# EVK-IRIS-W1-DEBUG_INTERFACE.net
KiCad netlist of a schematic drawn in Altium Designer
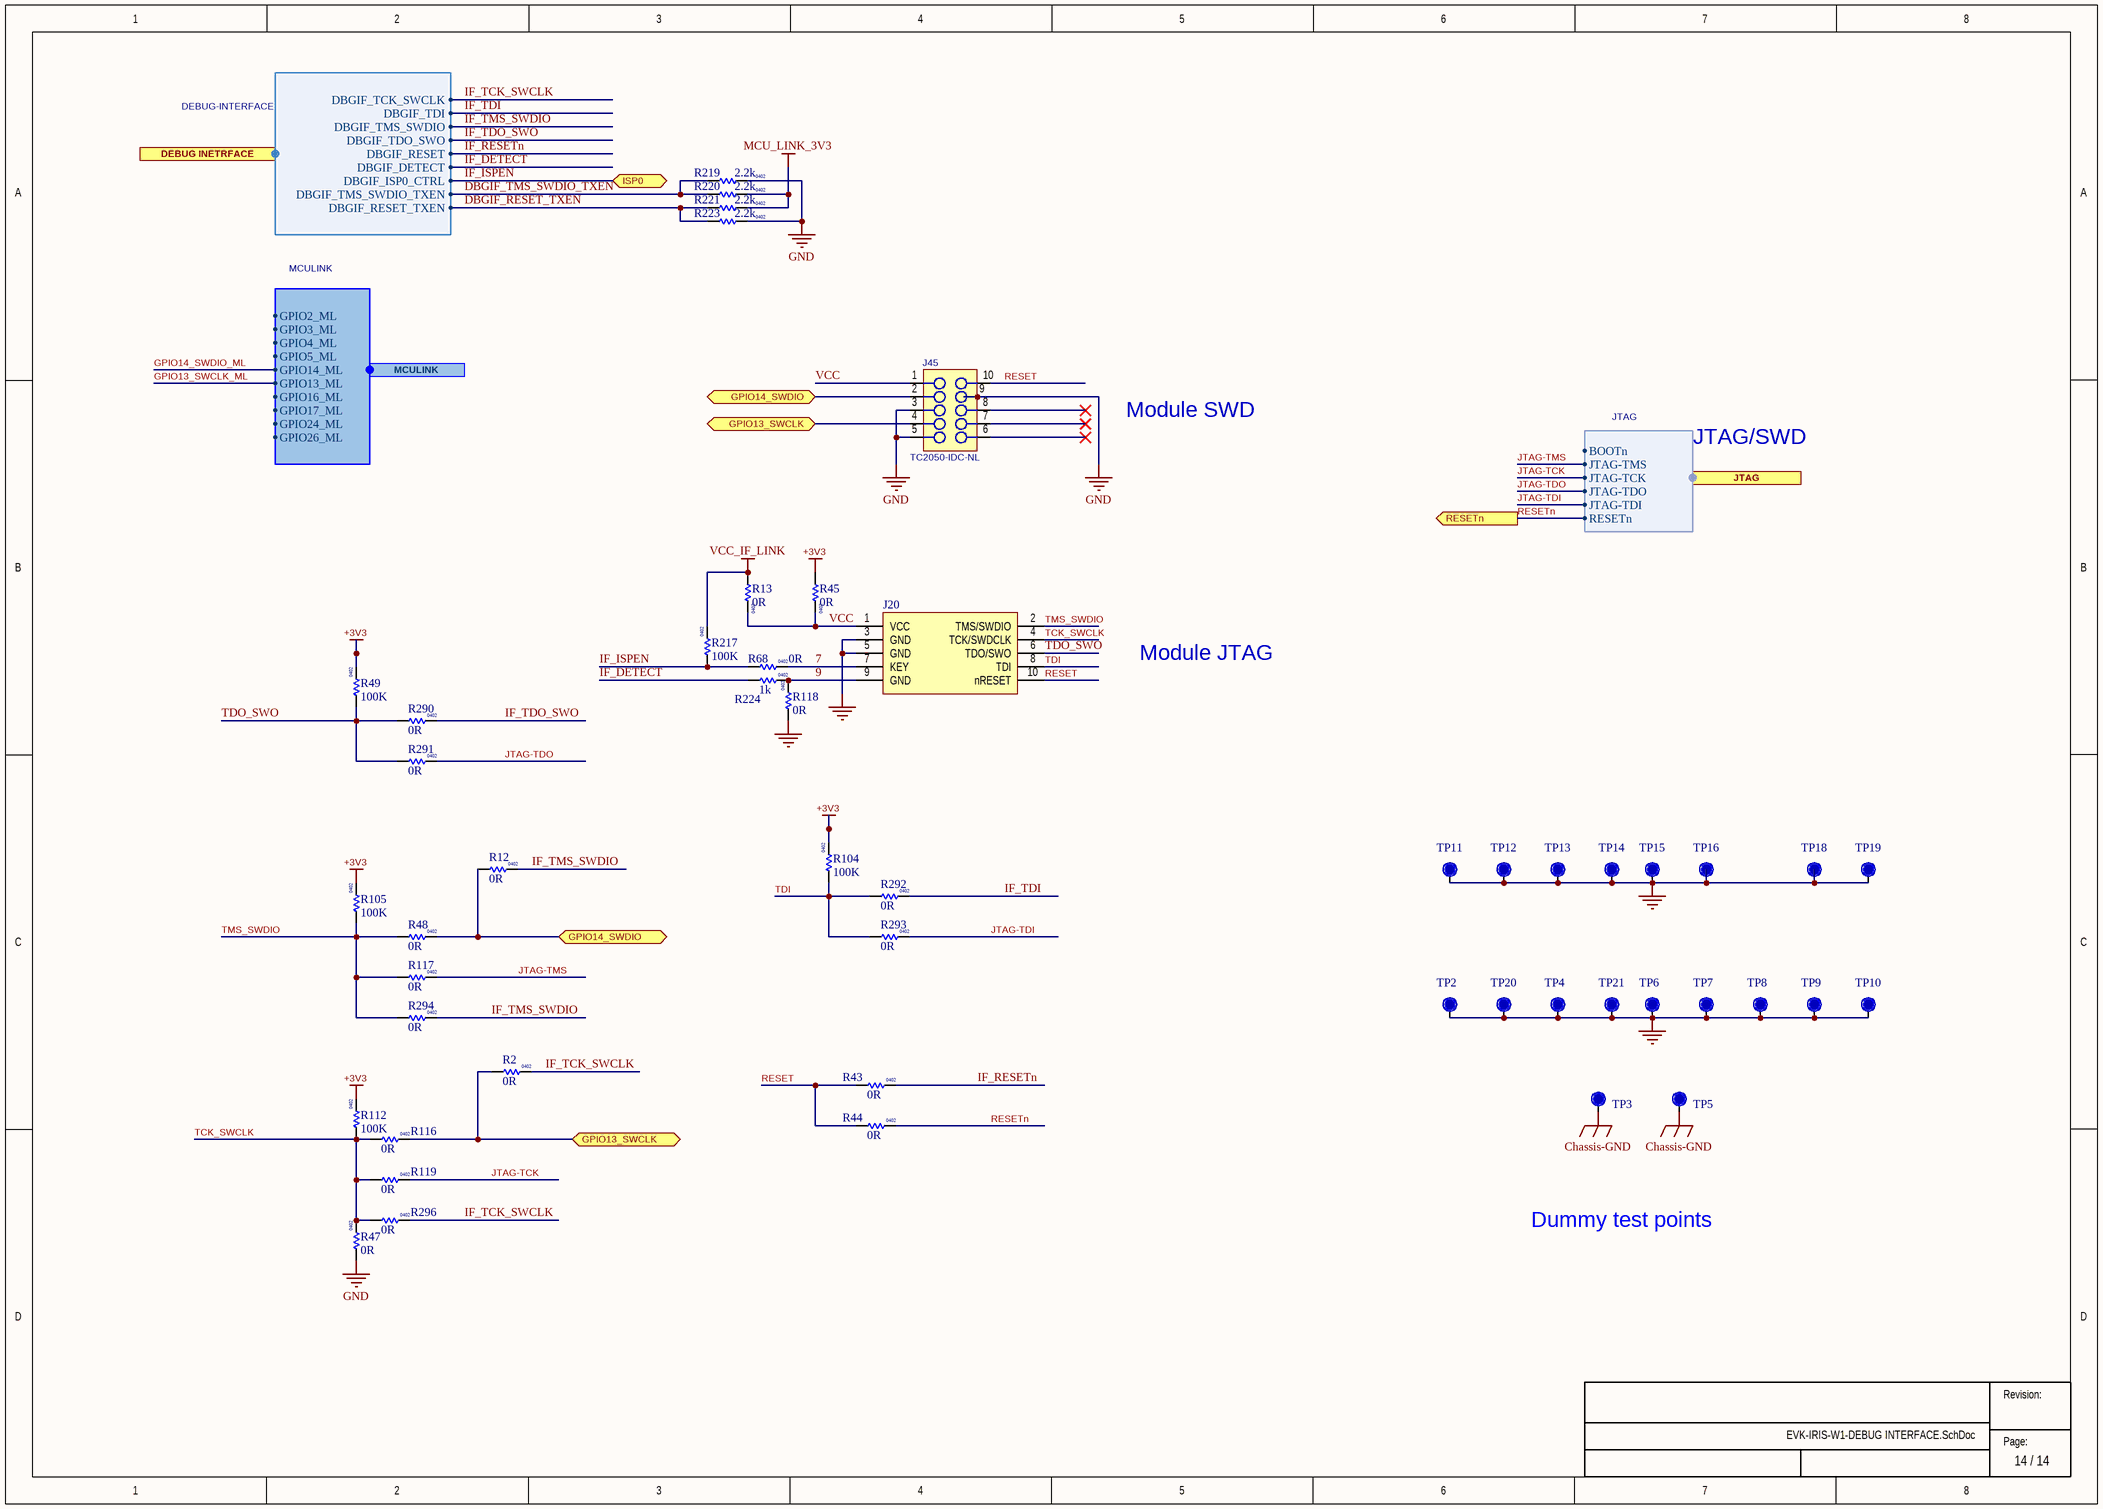
[diagram p0: EVK-IRIS-W1-DEBUG INTERFACE.SchDoc]

(export (version "E")
  (design (tool "Eeschema 10.0.6"))
  (components
    (comp (ref "J20")
      (value "130-00099")
      (footprint "HDR.050P-10Pin-2x5-SMT_Key")
      (description "Header 0.05\" 10Pin 2Row SMD Black")
      (fields (field (name "VOLTAGE") "None"))
      (libsource (lib "Arena_Parts_DB_Lib") (part "JTAG-10Pin"))
    )
    (comp (ref "J45")
      (value "TC2050-IDC-NLDNP")
      (footprint "TC2050-IDC-NL")
      (description "CON PADS FOR CBL PLUG-OF-NAILS 10-PIN NO LEGS")
      (fields
        (field (name "MANUFACTURER P/N") "TC2050-IDC-NL")
        (field (name "PART NUMBER") "TC2050-IDC-NL")
        (field (name "MANUFACTURER") "TAG Connect")
        (field (name "ADDED BY") "Paul B")
      )
      (libsource (lib "LEGACY_Rigado_AltiumLib") (part "CON-10Pin_2Row_ALT"))
    )
    (comp (ref "R2")
      (value "0R")
      (footprint "RES 0402 HD")
      (description "RES THICK FILM CHIP 0402 0R 0 100mW")
      (fields
        (field (name "SIZE") "0402")
        (field (name "PART NUMBER") "UBXH18-0003002")
        (field (name "TOLERANCE") "0")
        (field (name "EDITOR") "charlotte.biber")
        (field (name "RELEASED BY") "peter.mueller")
      )
      (libsource (lib "UBX_Parts_DB_Lib") (part "Res sm"))
    )
    (comp (ref "R12")
      (value "0R")
      (footprint "RES 0402 HD")
      (description "RES THICK FILM CHIP 0402 0R 0 100mW")
      (fields
        (field (name "SIZE") "0402")
        (field (name "PART NUMBER") "UBXH18-0003002")
        (field (name "TOLERANCE") "0")
        (field (name "EDITOR") "charlotte.biber")
        (field (name "RELEASED BY") "peter.mueller")
      )
      (libsource (lib "UBX_Parts_DB_Lib") (part "Res sm"))
    )
    (comp (ref "R13")
      (value "0R")
      (footprint "RES 0402 HD")
      (description "RES THICK FILM CHIP 0402 0R 0 100mW")
      (fields
        (field (name "SIZE") "0402")
        (field (name "PART NUMBER") "UBXH18-0003002")
        (field (name "TOLERANCE") "0")
        (field (name "EDITOR") "charlotte.biber")
        (field (name "RELEASED BY") "peter.mueller")
      )
      (libsource (lib "UBX_Parts_DB_Lib") (part "Res sm"))
    )
    (comp (ref "R43")
      (value "0R")
      (footprint "RES 0402 HD")
      (description "RES THICK FILM CHIP 0402 0R 0 100mW")
      (fields
        (field (name "SIZE") "0402")
        (field (name "PART NUMBER") "UBXH18-0003002")
        (field (name "TOLERANCE") "0")
        (field (name "EDITOR") "charlotte.biber")
        (field (name "RELEASED BY") "peter.mueller")
      )
      (libsource (lib "UBX_Parts_DB_Lib") (part "Res sm"))
    )
    (comp (ref "R44")
      (value "0R")
      (footprint "RES 0402 HD")
      (description "RES THICK FILM CHIP 0402 0R 0 100mW")
      (fields
        (field (name "SIZE") "0402")
        (field (name "PART NUMBER") "UBXH18-0003002")
        (field (name "TOLERANCE") "0")
        (field (name "EDITOR") "charlotte.biber")
        (field (name "RELEASED BY") "peter.mueller")
      )
      (libsource (lib "UBX_Parts_DB_Lib") (part "Res sm"))
    )
    (comp (ref "R45")
      (value "0R")
      (footprint "RES 0402 HD")
      (description "RES THICK FILM CHIP 0402 0R 0 100mW")
      (fields
        (field (name "SIZE") "0402")
        (field (name "PART NUMBER") "UBXH18-0003002")
        (field (name "TOLERANCE") "0")
        (field (name "EDITOR") "charlotte.biber")
        (field (name "RELEASED BY") "peter.mueller")
      )
      (libsource (lib "UBX_Parts_DB_Lib") (part "Res sm"))
    )
    (comp (ref "R47")
      (value "0R")
      (footprint "RES 0402 HD")
      (description "RES THICK FILM CHIP 0402 0R 0 100mW")
      (fields
        (field (name "SIZE") "0402")
        (field (name "PART NUMBER") "UBXH18-0003002")
        (field (name "TOLERANCE") "0")
        (field (name "EDITOR") "charlotte.biber")
        (field (name "RELEASED BY") "peter.mueller")
      )
      (libsource (lib "UBX_Parts_DB_Lib") (part "Res sm"))
    )
    (comp (ref "R48")
      (value "0R")
      (footprint "RES 0402 HD")
      (description "RES THICK FILM CHIP 0402 0R 0 100mW")
      (fields
        (field (name "SIZE") "0402")
        (field (name "PART NUMBER") "UBXH18-0003002")
        (field (name "TOLERANCE") "0")
        (field (name "EDITOR") "charlotte.biber")
        (field (name "RELEASED BY") "peter.mueller")
      )
      (libsource (lib "UBX_Parts_DB_Lib") (part "Res sm"))
    )
    (comp (ref "R49")
      (value "100K")
      (footprint "RES 0402 HD")
      (description "RES THICK FILM CHIP 0402 100K 1% 63mW")
      (fields
        (field (name "SIZE") "0402")
        (field (name "PART NUMBER") "UBXH18-0000005")
        (field (name "TOLERANCE") "1%")
        (field (name "EDITOR") "dario.antonaz")
        (field (name "RELEASED BY") "sandro.sestan")
      )
      (libsource (lib "UBX_Parts_DB_Lib") (part "Res sm"))
    )
    (comp (ref "R68")
      (value "0R")
      (footprint "RES 0402 HD")
      (description "RES THICK FILM CHIP 0402 0R 0 100mW")
      (fields
        (field (name "SIZE") "0402")
        (field (name "PART NUMBER") "UBXH18-0003002")
        (field (name "TOLERANCE") "0")
        (field (name "EDITOR") "charlotte.biber")
        (field (name "RELEASED BY") "peter.mueller")
      )
      (libsource (lib "UBX_Parts_DB_Lib") (part "Res sm"))
    )
    (comp (ref "R104")
      (value "100K")
      (footprint "RES 0402 HD")
      (description "RES THICK FILM CHIP 0402 100K 1% 63mW")
      (fields
        (field (name "SIZE") "0402")
        (field (name "PART NUMBER") "UBXH18-0000005")
        (field (name "TOLERANCE") "1%")
        (field (name "EDITOR") "dario.antonaz")
        (field (name "RELEASED BY") "sandro.sestan")
      )
      (libsource (lib "UBX_Parts_DB_Lib") (part "Res sm"))
    )
    (comp (ref "R105")
      (value "100K")
      (footprint "RES 0402 HD")
      (description "RES THICK FILM CHIP 0402 100K 1% 63mW")
      (fields
        (field (name "SIZE") "0402")
        (field (name "PART NUMBER") "UBXH18-0000005")
        (field (name "TOLERANCE") "1%")
        (field (name "EDITOR") "dario.antonaz")
        (field (name "RELEASED BY") "sandro.sestan")
      )
      (libsource (lib "UBX_Parts_DB_Lib") (part "Res sm"))
    )
    (comp (ref "R112")
      (value "100K")
      (footprint "RES 0402 HD")
      (description "RES THICK FILM CHIP 0402 100K 1% 63mW")
      (fields
        (field (name "SIZE") "0402")
        (field (name "PART NUMBER") "UBXH18-0000005")
        (field (name "TOLERANCE") "1%")
        (field (name "EDITOR") "dario.antonaz")
        (field (name "RELEASED BY") "sandro.sestan")
      )
      (libsource (lib "UBX_Parts_DB_Lib") (part "Res sm"))
    )
    (comp (ref "R116")
      (value "0R")
      (footprint "RES 0402 HD")
      (description "RES THICK FILM CHIP 0402 0R 0 100mW")
      (fields
        (field (name "SIZE") "0402")
        (field (name "PART NUMBER") "UBXH18-0003002")
        (field (name "TOLERANCE") "0")
        (field (name "EDITOR") "charlotte.biber")
        (field (name "RELEASED BY") "peter.mueller")
      )
      (libsource (lib "UBX_Parts_DB_Lib") (part "Res sm"))
    )
    (comp (ref "R117")
      (value "0R")
      (footprint "RES 0402 HD")
      (description "RES THICK FILM CHIP 0402 0R 0 100mW")
      (fields
        (field (name "SIZE") "0402")
        (field (name "PART NUMBER") "UBXH18-0003002")
        (field (name "TOLERANCE") "0")
        (field (name "EDITOR") "charlotte.biber")
        (field (name "RELEASED BY") "peter.mueller")
      )
      (libsource (lib "UBX_Parts_DB_Lib") (part "Res sm"))
    )
    (comp (ref "R118")
      (value "0R")
      (footprint "RES 0402 HD")
      (description "RES THICK FILM CHIP 0402 0R 0 100mW")
      (fields
        (field (name "SIZE") "0402")
        (field (name "PART NUMBER") "UBXH18-0003002")
        (field (name "TOLERANCE") "0")
        (field (name "EDITOR") "charlotte.biber")
        (field (name "RELEASED BY") "peter.mueller")
      )
      (libsource (lib "UBX_Parts_DB_Lib") (part "Res sm"))
    )
    (comp (ref "R119")
      (value "0R")
      (footprint "RES 0402 HD")
      (description "RES THICK FILM CHIP 0402 0R 0 100mW")
      (fields
        (field (name "SIZE") "0402")
        (field (name "PART NUMBER") "UBXH18-0003002")
        (field (name "TOLERANCE") "0")
        (field (name "EDITOR") "charlotte.biber")
        (field (name "RELEASED BY") "peter.mueller")
      )
      (libsource (lib "UBX_Parts_DB_Lib") (part "Res sm"))
    )
    (comp (ref "R217")
      (value "100K")
      (footprint "RES 0402 HD")
      (description "RES THICK FILM CHIP 0402 100K 1% 63mW")
      (fields
        (field (name "SIZE") "0402")
        (field (name "PART NUMBER") "UBXH18-0000005")
        (field (name "TOLERANCE") "1%")
        (field (name "EDITOR") "dario.antonaz")
        (field (name "RELEASED BY") "sandro.sestan")
      )
      (libsource (lib "UBX_Parts_DB_Lib") (part "Res sm"))
    )
    (comp (ref "R219")
      (value "2.2k")
      (footprint "RES 0402 HD")
      (description "Resistor, 2.2Kohm, 1%, 1/16W, 0402")
      (fields
        (field (name "SIZE") "0402")
        (field (name "PART NUMBER") "180-00023")
        (field (name "POWER") "1/16W")
      )
      (libsource (lib "Arena_Parts_DB_Lib") (part "Res sm"))
    )
    (comp (ref "R220")
      (value "2.2k")
      (footprint "RES 0402 HD")
      (description "Resistor, 2.2Kohm, 1%, 1/16W, 0402")
      (fields
        (field (name "SIZE") "0402")
        (field (name "PART NUMBER") "180-00023")
        (field (name "POWER") "1/16W")
      )
      (libsource (lib "Arena_Parts_DB_Lib") (part "Res sm"))
    )
    (comp (ref "R221")
      (value "2.2k")
      (footprint "RES 0402 HD")
      (description "Resistor, 2.2Kohm, 1%, 1/16W, 0402")
      (fields
        (field (name "SIZE") "0402")
        (field (name "PART NUMBER") "180-00023")
        (field (name "POWER") "1/16W")
      )
      (libsource (lib "Arena_Parts_DB_Lib") (part "Res sm"))
    )
    (comp (ref "R223")
      (value "2.2k")
      (footprint "RES 0402 HD")
      (description "Resistor, 2.2Kohm, 1%, 1/16W, 0402")
      (fields
        (field (name "SIZE") "0402")
        (field (name "PART NUMBER") "180-00023")
        (field (name "POWER") "1/16W")
      )
      (libsource (lib "Arena_Parts_DB_Lib") (part "Res sm"))
    )
    (comp (ref "R224")
      (value "1k")
      (footprint "RES 0402 HD")
      (description "Resistor 1k ohm 1% 1/16W, 0402")
      (fields
        (field (name "SIZE") "0402")
        (field (name "PART NUMBER") "180-00021")
        (field (name "POWER") "1/16W")
      )
      (libsource (lib "Arena_Parts_DB_Lib") (part "Res sm"))
    )
    (comp (ref "R290")
      (value "0R")
      (footprint "RES 0402 HD")
      (description "RES THICK FILM CHIP 0402 0R 0 100mW")
      (fields
        (field (name "SIZE") "0402")
        (field (name "PART NUMBER") "UBXH18-0003002")
        (field (name "TOLERANCE") "0")
        (field (name "EDITOR") "charlotte.biber")
        (field (name "RELEASED BY") "peter.mueller")
      )
      (libsource (lib "UBX_Parts_DB_Lib") (part "Res sm"))
    )
    (comp (ref "R291")
      (value "0R")
      (footprint "RES 0402 HD")
      (description "RES THICK FILM CHIP 0402 0R 0 100mW")
      (fields
        (field (name "SIZE") "0402")
        (field (name "PART NUMBER") "UBXH18-0003002")
        (field (name "TOLERANCE") "0")
        (field (name "EDITOR") "charlotte.biber")
        (field (name "RELEASED BY") "peter.mueller")
      )
      (libsource (lib "UBX_Parts_DB_Lib") (part "Res sm"))
    )
    (comp (ref "R292")
      (value "0R")
      (footprint "RES 0402 HD")
      (description "RES THICK FILM CHIP 0402 0R 0 100mW")
      (fields
        (field (name "SIZE") "0402")
        (field (name "PART NUMBER") "UBXH18-0003002")
        (field (name "TOLERANCE") "0")
        (field (name "EDITOR") "charlotte.biber")
        (field (name "RELEASED BY") "peter.mueller")
      )
      (libsource (lib "UBX_Parts_DB_Lib") (part "Res sm"))
    )
    (comp (ref "R293")
      (value "0R")
      (footprint "RES 0402 HD")
      (description "RES THICK FILM CHIP 0402 0R 0 100mW")
      (fields
        (field (name "SIZE") "0402")
        (field (name "PART NUMBER") "UBXH18-0003002")
        (field (name "TOLERANCE") "0")
        (field (name "EDITOR") "charlotte.biber")
        (field (name "RELEASED BY") "peter.mueller")
      )
      (libsource (lib "UBX_Parts_DB_Lib") (part "Res sm"))
    )
    (comp (ref "R294")
      (value "0R")
      (footprint "RES 0402 HD")
      (description "RES THICK FILM CHIP 0402 0R 0 100mW")
      (fields
        (field (name "SIZE") "0402")
        (field (name "PART NUMBER") "UBXH18-0003002")
        (field (name "TOLERANCE") "0")
        (field (name "EDITOR") "charlotte.biber")
        (field (name "RELEASED BY") "peter.mueller")
      )
      (libsource (lib "UBX_Parts_DB_Lib") (part "Res sm"))
    )
    (comp (ref "R296")
      (value "0R")
      (footprint "RES 0402 HD")
      (description "RES THICK FILM CHIP 0402 0R 0 100mW")
      (fields
        (field (name "SIZE") "0402")
        (field (name "PART NUMBER") "UBXH18-0003002")
        (field (name "TOLERANCE") "0")
        (field (name "EDITOR") "charlotte.biber")
        (field (name "RELEASED BY") "peter.mueller")
      )
      (libsource (lib "UBX_Parts_DB_Lib") (part "Res sm"))
    )
    (comp (ref "TP2")
      (value "TP")
      (footprint "TP10R")
      (description "Testpoint, Round 1.0mm Dia")
      (fields
        (field (name "PART NUMBER") "TP10R")
        (field (name "ADDED BY") "Jeremy D")
        (field (name "CHECKED BY") "Paul B")
      )
      (libsource (lib "LEGACY_Rigado_AltiumLib") (part "TP_R"))
    )
    (comp (ref "TP3")
      (value "TP")
      (footprint "TP10R")
      (description "Testpoint, Round 1.0mm Dia")
      (fields
        (field (name "PART NUMBER") "TP10R")
        (field (name "ADDED BY") "Jeremy D")
        (field (name "CHECKED BY") "Paul B")
      )
      (libsource (lib "LEGACY_Rigado_AltiumLib") (part "TP_R"))
    )
    (comp (ref "TP4")
      (value "TP")
      (footprint "TP10R")
      (description "Testpoint, Round 1.0mm Dia")
      (fields
        (field (name "PART NUMBER") "TP10R")
        (field (name "ADDED BY") "Jeremy D")
        (field (name "CHECKED BY") "Paul B")
      )
      (libsource (lib "LEGACY_Rigado_AltiumLib") (part "TP_R"))
    )
    (comp (ref "TP5")
      (value "TP")
      (footprint "TP10R")
      (description "Testpoint, Round 1.0mm Dia")
      (fields
        (field (name "PART NUMBER") "TP10R")
        (field (name "ADDED BY") "Jeremy D")
        (field (name "CHECKED BY") "Paul B")
      )
      (libsource (lib "LEGACY_Rigado_AltiumLib") (part "TP_R"))
    )
    (comp (ref "TP6")
      (value "TP")
      (footprint "TP10R")
      (description "Testpoint, Round 1.0mm Dia")
      (fields
        (field (name "PART NUMBER") "TP10R")
        (field (name "ADDED BY") "Jeremy D")
        (field (name "CHECKED BY") "Paul B")
      )
      (libsource (lib "LEGACY_Rigado_AltiumLib") (part "TP_R"))
    )
    (comp (ref "TP7")
      (value "TP")
      (footprint "TP10R")
      (description "Testpoint, Round 1.0mm Dia")
      (fields
        (field (name "PART NUMBER") "TP10R")
        (field (name "ADDED BY") "Jeremy D")
        (field (name "CHECKED BY") "Paul B")
      )
      (libsource (lib "LEGACY_Rigado_AltiumLib") (part "TP_R"))
    )
    (comp (ref "TP8")
      (value "TP")
      (footprint "TP10R")
      (description "Testpoint, Round 1.0mm Dia")
      (fields
        (field (name "PART NUMBER") "TP10R")
        (field (name "ADDED BY") "Jeremy D")
        (field (name "CHECKED BY") "Paul B")
      )
      (libsource (lib "LEGACY_Rigado_AltiumLib") (part "TP_R"))
    )
    (comp (ref "TP9")
      (value "TP")
      (footprint "TP10R")
      (description "Testpoint, Round 1.0mm Dia")
      (fields
        (field (name "PART NUMBER") "TP10R")
        (field (name "ADDED BY") "Jeremy D")
        (field (name "CHECKED BY") "Paul B")
      )
      (libsource (lib "LEGACY_Rigado_AltiumLib") (part "TP_R"))
    )
    (comp (ref "TP10")
      (value "TP")
      (footprint "TP10R")
      (description "Testpoint, Round 1.0mm Dia")
      (fields
        (field (name "PART NUMBER") "TP10R")
        (field (name "ADDED BY") "Jeremy D")
        (field (name "CHECKED BY") "Paul B")
      )
      (libsource (lib "LEGACY_Rigado_AltiumLib") (part "TP_R"))
    )
    (comp (ref "TP11")
      (value "TP")
      (footprint "TP10R")
      (description "Testpoint, Round 1.0mm Dia")
      (fields
        (field (name "PART NUMBER") "TP10R")
        (field (name "ADDED BY") "Jeremy D")
        (field (name "CHECKED BY") "Paul B")
      )
      (libsource (lib "LEGACY_Rigado_AltiumLib") (part "TP_R"))
    )
    (comp (ref "TP12")
      (value "TP")
      (footprint "TP10R")
      (description "Testpoint, Round 1.0mm Dia")
      (fields
        (field (name "PART NUMBER") "TP10R")
        (field (name "ADDED BY") "Jeremy D")
        (field (name "CHECKED BY") "Paul B")
      )
      (libsource (lib "LEGACY_Rigado_AltiumLib") (part "TP_R"))
    )
    (comp (ref "TP13")
      (value "TP")
      (footprint "TP10R")
      (description "Testpoint, Round 1.0mm Dia")
      (fields
        (field (name "PART NUMBER") "TP10R")
        (field (name "ADDED BY") "Jeremy D")
        (field (name "CHECKED BY") "Paul B")
      )
      (libsource (lib "LEGACY_Rigado_AltiumLib") (part "TP_R"))
    )
    (comp (ref "TP14")
      (value "TP")
      (footprint "TP10R")
      (description "Testpoint, Round 1.0mm Dia")
      (fields
        (field (name "PART NUMBER") "TP10R")
        (field (name "ADDED BY") "Jeremy D")
        (field (name "CHECKED BY") "Paul B")
      )
      (libsource (lib "LEGACY_Rigado_AltiumLib") (part "TP_R"))
    )
    (comp (ref "TP15")
      (value "TP")
      (footprint "TP10R")
      (description "Testpoint, Round 1.0mm Dia")
      (fields
        (field (name "PART NUMBER") "TP10R")
        (field (name "ADDED BY") "Jeremy D")
        (field (name "CHECKED BY") "Paul B")
      )
      (libsource (lib "LEGACY_Rigado_AltiumLib") (part "TP_R"))
    )
    (comp (ref "TP16")
      (value "TP")
      (footprint "TP10R")
      (description "Testpoint, Round 1.0mm Dia")
      (fields
        (field (name "PART NUMBER") "TP10R")
        (field (name "ADDED BY") "Jeremy D")
        (field (name "CHECKED BY") "Paul B")
      )
      (libsource (lib "LEGACY_Rigado_AltiumLib") (part "TP_R"))
    )
    (comp (ref "TP18")
      (value "TP")
      (footprint "TP10R")
      (description "Testpoint, Round 1.0mm Dia")
      (fields
        (field (name "PART NUMBER") "TP10R")
        (field (name "ADDED BY") "Jeremy D")
        (field (name "CHECKED BY") "Paul B")
      )
      (libsource (lib "LEGACY_Rigado_AltiumLib") (part "TP_R"))
    )
    (comp (ref "TP19")
      (value "TP")
      (footprint "TP10R")
      (description "Testpoint, Round 1.0mm Dia")
      (fields
        (field (name "PART NUMBER") "TP10R")
        (field (name "ADDED BY") "Jeremy D")
        (field (name "CHECKED BY") "Paul B")
      )
      (libsource (lib "LEGACY_Rigado_AltiumLib") (part "TP_R"))
    )
    (comp (ref "TP20")
      (value "TP")
      (footprint "TP10R")
      (description "Testpoint, Round 1.0mm Dia")
      (fields
        (field (name "PART NUMBER") "TP10R")
        (field (name "ADDED BY") "Jeremy D")
        (field (name "CHECKED BY") "Paul B")
      )
      (libsource (lib "LEGACY_Rigado_AltiumLib") (part "TP_R"))
    )
    (comp (ref "TP21")
      (value "TP")
      (footprint "TP10R")
      (description "Testpoint, Round 1.0mm Dia")
      (fields
        (field (name "PART NUMBER") "TP10R")
        (field (name "ADDED BY") "Jeremy D")
        (field (name "CHECKED BY") "Paul B")
      )
      (libsource (lib "LEGACY_Rigado_AltiumLib") (part "TP_R"))
    )
  )
  (nets
    (net (code "4") (name "+3V3") (class "Default")
      (node (ref "R104") (pin "2") (pinfunction "2_2") (pintype "passive"))
      (node (ref "R105") (pin "2") (pinfunction "2_2") (pintype "passive"))
      (node (ref "R112") (pin "2") (pinfunction "2_2") (pintype "passive"))
      (node (ref "R45") (pin "1") (pinfunction "1_1") (pintype "passive"))
      (node (ref "R49") (pin "2") (pinfunction "2_2") (pintype "passive"))
    )
    (net (code "5") (name "/7") (class "Default")
      (node (ref "J20") (pin "7") (pinfunction "KEY_7") (pintype "passive"))
      (node (ref "R68") (pin "2") (pinfunction "2_2") (pintype "passive"))
    )
    (net (code "6") (name "/9") (class "Default")
      (node (ref "J20") (pin "9") (pinfunction "GND_9") (pintype "passive"))
      (node (ref "R118") (pin "2") (pinfunction "2_2") (pintype "passive"))
      (node (ref "R224") (pin "2") (pinfunction "2_2") (pintype "passive"))
    )
    (net (code "7") (name "/DBGIF_RESET_TXEN") (class "Default")
      (node (ref "R221") (pin "1") (pinfunction "1_1") (pintype "passive"))
      (node (ref "R223") (pin "1") (pinfunction "1_1") (pintype "passive"))
    )
    (net (code "8") (name "/DBGIF_TMS_SWDIO_TXEN") (class "Default")
      (node (ref "R219") (pin "1") (pinfunction "1_1") (pintype "passive"))
      (node (ref "R220") (pin "2") (pinfunction "2_2") (pintype "passive"))
    )
    (net (code "9") (name "/GPIO13_SWCLK") (class "Default")
      (node (ref "J45") (pin "4") (pintype "passive"))
      (node (ref "R116") (pin "2") (pinfunction "2_2") (pintype "passive"))
      (node (ref "R2") (pin "1") (pinfunction "1_1") (pintype "passive"))
    )
    (net (code "11") (name "/GPIO14_SWDIO") (class "Default")
      (node (ref "J45") (pin "2") (pintype "passive"))
      (node (ref "R12") (pin "1") (pinfunction "1_1") (pintype "passive"))
      (node (ref "R48") (pin "2") (pinfunction "2_2") (pintype "passive"))
    )
    (net (code "13") (name "/IF_DETECT") (class "Default")
      (node (ref "R224") (pin "1") (pinfunction "1_1") (pintype "passive"))
    )
    (net (code "14") (name "/IF_ISPEN") (class "Default")
      (node (ref "R217") (pin "1") (pinfunction "1_1") (pintype "passive"))
      (node (ref "R68") (pin "1") (pinfunction "1_1") (pintype "passive"))
    )
    (net (code "15") (name "/IF_RESETn") (class "Default")
      (node (ref "R43") (pin "2") (pinfunction "2_2") (pintype "passive"))
    )
    (net (code "16") (name "/IF_TCK_SWCLK") (class "Default")
      (node (ref "R2") (pin "2") (pinfunction "2_2") (pintype "passive"))
      (node (ref "R296") (pin "2") (pinfunction "2_2") (pintype "passive"))
    )
    (net (code "17") (name "/IF_TDI") (class "Default")
      (node (ref "R292") (pin "2") (pinfunction "2_2") (pintype "passive"))
    )
    (net (code "18") (name "/IF_TDO_SWO") (class "Default")
      (node (ref "R290") (pin "2") (pinfunction "2_2") (pintype "passive"))
    )
    (net (code "19") (name "/IF_TMS_SWDIO") (class "Default")
      (node (ref "R12") (pin "2") (pinfunction "2_2") (pintype "passive"))
      (node (ref "R294") (pin "2") (pinfunction "2_2") (pintype "passive"))
    )
    (net (code "20") (name "/JTAG-TCK") (class "Default")
      (node (ref "R119") (pin "2") (pinfunction "2_2") (pintype "passive"))
    )
    (net (code "21") (name "/JTAG-TDI") (class "Default")
      (node (ref "R293") (pin "2") (pinfunction "2_2") (pintype "passive"))
    )
    (net (code "22") (name "/JTAG-TDO") (class "Default")
      (node (ref "R291") (pin "2") (pinfunction "2_2") (pintype "passive"))
    )
    (net (code "23") (name "/JTAG-TMS") (class "Default")
      (node (ref "R117") (pin "2") (pinfunction "2_2") (pintype "passive"))
    )
    (net (code "24") (name "/RESET") (class "Default")
      (node (ref "J20") (pin "10") (pinfunction "nRESET_10") (pintype "passive"))
      (node (ref "J45") (pin "10") (pintype "passive"))
      (node (ref "R43") (pin "1") (pinfunction "1_1") (pintype "passive"))
      (node (ref "R44") (pin "1") (pinfunction "1_1") (pintype "passive"))
    )
    (net (code "25") (name "/RESETn") (class "Default")
      (node (ref "R44") (pin "2") (pinfunction "2_2") (pintype "passive"))
    )
    (net (code "26") (name "/TCK_SWCLK") (class "Default")
      (node (ref "J20") (pin "4") (pinfunction "TCK/SWDCLK_4") (pintype "passive"))
      (node (ref "R112") (pin "1") (pinfunction "1_1") (pintype "passive"))
      (node (ref "R116") (pin "1") (pinfunction "1_1") (pintype "passive"))
      (node (ref "R119") (pin "1") (pinfunction "1_1") (pintype "passive"))
      (node (ref "R296") (pin "1") (pinfunction "1_1") (pintype "passive"))
      (node (ref "R47") (pin "2") (pinfunction "2_2") (pintype "passive"))
    )
    (net (code "27") (name "/TDI") (class "Default")
      (node (ref "J20") (pin "8") (pinfunction "TDI_8") (pintype "passive"))
      (node (ref "R104") (pin "1") (pinfunction "1_1") (pintype "passive"))
      (node (ref "R292") (pin "1") (pinfunction "1_1") (pintype "passive"))
      (node (ref "R293") (pin "1") (pinfunction "1_1") (pintype "passive"))
    )
    (net (code "28") (name "/TDO_SWO") (class "Default")
      (node (ref "J20") (pin "6") (pinfunction "TDO/SWO_6") (pintype "passive"))
      (node (ref "R290") (pin "1") (pinfunction "1_1") (pintype "passive"))
      (node (ref "R291") (pin "1") (pinfunction "1_1") (pintype "passive"))
      (node (ref "R49") (pin "1") (pinfunction "1_1") (pintype "passive"))
    )
    (net (code "29") (name "/TMS_SWDIO") (class "Default")
      (node (ref "J20") (pin "2") (pinfunction "TMS/SWDIO_2") (pintype "passive"))
      (node (ref "R105") (pin "1") (pinfunction "1_1") (pintype "passive"))
      (node (ref "R117") (pin "1") (pinfunction "1_1") (pintype "passive"))
      (node (ref "R294") (pin "1") (pinfunction "1_1") (pintype "passive"))
      (node (ref "R48") (pin "1") (pinfunction "1_1") (pintype "passive"))
    )
    (net (code "30") (name "/VCC") (class "Default")
      (node (ref "J20") (pin "1") (pinfunction "VCC_1") (pintype "passive"))
      (node (ref "J45") (pin "1") (pintype "passive"))
      (node (ref "R13") (pin "2") (pinfunction "2_2") (pintype "passive"))
      (node (ref "R45") (pin "2") (pinfunction "2_2") (pintype "passive"))
    )
    (net (code "34") (name "Chassis-GND") (class "Default")
      (node (ref "TP3") (pin "1") (pintype "passive"))
      (node (ref "TP5") (pin "1") (pintype "passive"))
    )
    (net (code "35") (name "GND") (class "Default")
      (node (ref "J20") (pin "3") (pinfunction "GND_3") (pintype "passive"))
      (node (ref "J20") (pin "5") (pinfunction "GND_5") (pintype "passive"))
      (node (ref "J45") (pin "3") (pintype "passive"))
      (node (ref "J45") (pin "5") (pintype "passive"))
      (node (ref "J45") (pin "9") (pintype "passive"))
      (node (ref "R118") (pin "1") (pinfunction "1_1") (pintype "passive"))
      (node (ref "R219") (pin "2") (pinfunction "2_2") (pintype "passive"))
      (node (ref "R223") (pin "2") (pinfunction "2_2") (pintype "passive"))
      (node (ref "R47") (pin "1") (pinfunction "1_1") (pintype "passive"))
      (node (ref "TP10") (pin "1") (pintype "passive"))
      (node (ref "TP11") (pin "1") (pintype "passive"))
      (node (ref "TP12") (pin "1") (pintype "passive"))
      (node (ref "TP13") (pin "1") (pintype "passive"))
      (node (ref "TP14") (pin "1") (pintype "passive"))
      (node (ref "TP15") (pin "1") (pintype "passive"))
      (node (ref "TP16") (pin "1") (pintype "passive"))
      (node (ref "TP18") (pin "1") (pintype "passive"))
      (node (ref "TP19") (pin "1") (pintype "passive"))
      (node (ref "TP2") (pin "1") (pintype "passive"))
      (node (ref "TP20") (pin "1") (pintype "passive"))
      (node (ref "TP21") (pin "1") (pintype "passive"))
      (node (ref "TP4") (pin "1") (pintype "passive"))
      (node (ref "TP6") (pin "1") (pintype "passive"))
      (node (ref "TP7") (pin "1") (pintype "passive"))
      (node (ref "TP8") (pin "1") (pintype "passive"))
      (node (ref "TP9") (pin "1") (pintype "passive"))
    )
    (net (code "36") (name "MCU_LINK_3V3") (class "Default")
      (node (ref "R220") (pin "1") (pinfunction "1_1") (pintype "passive"))
      (node (ref "R221") (pin "2") (pinfunction "2_2") (pintype "passive"))
    )
    (net (code "37") (name "VCC_IF_LINK") (class "Default")
      (node (ref "R13") (pin "1") (pinfunction "1_1") (pintype "passive"))
      (node (ref "R217") (pin "2") (pinfunction "2_2") (pintype "passive"))
    )
    (net (code "38") (name "unconnected-(J45-Pad6)") (class "Default")
      (node (ref "J45") (pin "6") (pintype "passive+no_connect"))
    )
    (net (code "39") (name "unconnected-(J45-Pad7)") (class "Default")
      (node (ref "J45") (pin "7") (pintype "passive+no_connect"))
    )
    (net (code "40") (name "unconnected-(J45-Pad8)") (class "Default")
      (node (ref "J45") (pin "8") (pintype "passive+no_connect"))
    )
  )
)
